# CS_JFETOnSemiSOT23_Simple_v1.net
KiCad netlist of a schematic drawn in Altium Designer
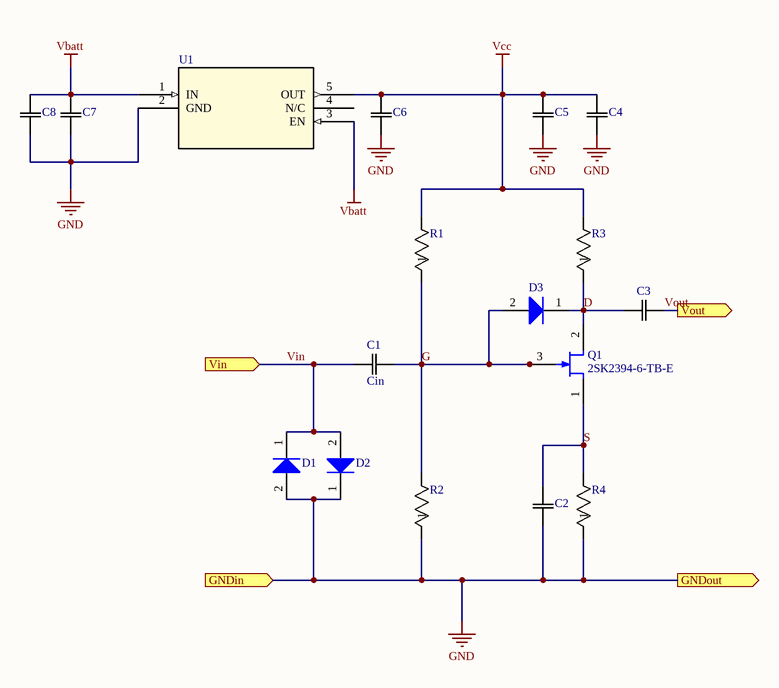
[diagram p0: CS_JFETOnSemiSOT23_Simple_v1.SchDoc]

(export (version "E")
  (design (tool "Eeschema 10.0.6"))
  (components
    (comp (ref "C1")
      (value "Cin")
      (footprint "C0201")
      (description "No Description Available")
      (fields
        (field (name "MANUFACTURER_PART_NUMBER") "C0201C270J3GACTU")
        (field (name "COPYRIGHT") "Copyright (C) 2018 Accelerated Designs. All rights reserved")
      )
      (libsource (lib "0201Capacitor_Yageo") (part "C0201C270J3GACTU"))
    )
    (comp (ref "C2")
      (value "~")
      (footprint "C0201")
      (description "No Description Available")
      (fields
        (field (name "MANUFACTURER_PART_NUMBER") "C0201C270J3GACTU")
        (field (name "COPYRIGHT") "Copyright (C) 2018 Accelerated Designs. All rights reserved")
      )
      (libsource (lib "0201Capacitor_Yageo") (part "C0201C270J3GACTU"))
    )
    (comp (ref "C3")
      (value "~")
      (footprint "C0201")
      (description "No Description Available")
      (fields
        (field (name "MANUFACTURER_PART_NUMBER") "C0201C270J3GACTU")
        (field (name "COPYRIGHT") "Copyright (C) 2018 Accelerated Designs. All rights reserved")
      )
      (libsource (lib "0201Capacitor_Yageo") (part "C0201C270J3GACTU"))
    )
    (comp (ref "C4")
      (value "~")
      (footprint "CAP_CBR_0201")
      (description "No Description Available")
      (fields
        (field (name "MANUFACTURER_PART_NUMBER") "CBR02C399C3GAC")
        (field (name "COPYRIGHT") "Copyright (C) 2018 Accelerated Designs. All rights reserved")
      )
      (libsource (lib "0201Capacitor_KEMET") (part "CBR02C399C3GAC"))
    )
    (comp (ref "C5")
      (value "~")
      (footprint "CAP_CBR_0201")
      (description "No Description Available")
      (fields
        (field (name "MANUFACTURER_PART_NUMBER") "CBR02C399C3GAC")
        (field (name "COPYRIGHT") "Copyright (C) 2018 Accelerated Designs. All rights reserved")
      )
      (libsource (lib "0201Capacitor_KEMET") (part "CBR02C399C3GAC"))
    )
    (comp (ref "C6")
      (value "~")
      (footprint "YAG_CC0402")
      (description "No Description Available")
      (fields
        (field (name "MANUFACTURER_PART_NUMBER") "CC0402KRX7R9BB103")
        (field (name "COPYRIGHT") "Copyright (C) 2018 Accelerated Designs. All rights reserved")
      )
      (libsource (lib "0402Capacitor_Yageo") (part "CC0402KRX7R9BB10"))
    )
    (comp (ref "C7")
      (value "~")
      (footprint "YAG_CC0402")
      (description "No Description Available")
      (fields
        (field (name "MANUFACTURER_PART_NUMBER") "CC0402KRX7R9BB103")
        (field (name "COPYRIGHT") "Copyright (C) 2018 Accelerated Designs. All rights reserved")
      )
      (libsource (lib "0402Capacitor_Yageo") (part "CC0402KRX7R9BB10"))
    )
    (comp (ref "C8")
      (value "~")
      (footprint "YAG_CC0402")
      (description "No Description Available")
      (fields
        (field (name "MANUFACTURER_PART_NUMBER") "CC0402KRX7R9BB103")
        (field (name "COPYRIGHT") "Copyright (C) 2018 Accelerated Designs. All rights reserved")
      )
      (libsource (lib "0402Capacitor_Yageo") (part "CC0402KRX7R9BB10"))
    )
    (comp (ref "D1")
      (value "~")
      (footprint "INF-SOD323_V")
      (description "Single Silicon Schottky Diode, 110 mA IF Max, SOD32, Green")
      (fields (field (name "MANUFACTURER") "Infineon") (field (name "PARTNUMBER") "BAT15-03W"))
      (libsource (lib "Infineon_RFSchottkyDiode_SOD323") (part "BAT15-03W"))
    )
    (comp (ref "D2")
      (value "~")
      (footprint "INF-SOD323_V")
      (description "Single Silicon Schottky Diode, 110 mA IF Max, SOD32, Green")
      (fields (field (name "MANUFACTURER") "Infineon") (field (name "PARTNUMBER") "BAT15-03W"))
      (libsource (lib "Infineon_RFSchottkyDiode_SOD323") (part "BAT15-03W"))
    )
    (comp (ref "D3")
      (value "~")
      (footprint "INF-SOD323_V")
      (description "Single Silicon Schottky Diode, 110 mA IF Max, SOD32, Green")
      (fields (field (name "MANUFACTURER") "Infineon") (field (name "PARTNUMBER") "BAT15-03W"))
      (libsource (lib "Infineon_RFSchottkyDiode_SOD323") (part "BAT15-03W"))
    )
    (comp (ref "Q1")
      (value "2SK2394-6-TB-E")
      (footprint "ONSC-CP-3-318AN_A_V")
      (description "N-Channel JFET, 15 V, 10 to 20 mA, 38 mS, 3-Pin CP, Pb-Free, Tape and Reel")
      (fields (field (name "MANUFACTURER") "On Semiconductor"))
      (libsource (lib "ON Semi JFETs") (part "2SK2394-6-TB-E"))
    )
    (comp (ref "R1")
      (value "~")
      (footprint "RES_RC0201_P6XP3")
      (description "No Description Available")
      (fields
        (field (name "MANUFACTURER_PART_NUMBER") "RC0201FR-0718KL")
        (field (name "COPYRIGHT") "Copyright (C) 2018 Accelerated Designs. All rights reserved")
      )
      (libsource (lib "0201Resistor_Yageo") (part "RC0201FR-0718KL"))
    )
    (comp (ref "R2")
      (value "~")
      (footprint "RES_RC0201_P6XP3")
      (description "No Description Available")
      (fields
        (field (name "MANUFACTURER_PART_NUMBER") "RC0201FR-0718KL")
        (field (name "COPYRIGHT") "Copyright (C) 2018 Accelerated Designs. All rights reserved")
      )
      (libsource (lib "0201Resistor_Yageo") (part "RC0201FR-0718KL"))
    )
    (comp (ref "R3")
      (value "~")
      (footprint "RES_RC0201_P6XP3")
      (description "No Description Available")
      (fields
        (field (name "MANUFACTURER_PART_NUMBER") "RC0201FR-0718KL")
        (field (name "COPYRIGHT") "Copyright (C) 2018 Accelerated Designs. All rights reserved")
      )
      (libsource (lib "0201Resistor_Yageo") (part "RC0201FR-0718KL"))
    )
    (comp (ref "R4")
      (value "~")
      (footprint "RES_RC0201_P6XP3")
      (description "No Description Available")
      (fields
        (field (name "MANUFACTURER_PART_NUMBER") "RC0201FR-0718KL")
        (field (name "COPYRIGHT") "Copyright (C) 2018 Accelerated Designs. All rights reserved")
      )
      (libsource (lib "0201Resistor_Yageo") (part "RC0201FR-0718KL"))
    )
    (comp (ref "U1")
      (value "~")
      (footprint "DBV5")
      (description "No Description Available")
      (fields
        (field (name "MANUFACTURER_PART_NUMBER") "LP5907MFX-3.3/NOPB")
        (field (name "COPYRIGHT") "Copyright (C) 2018 Accelerated Designs. All rights reserved")
      )
      (libsource (lib "TI_LDO_3V3_SOT325") (part "LP5907MFX-3.3/NO"))
    )
  )
  (nets
    (net (code "1") (name "/D") (class "Default")
      (node (ref "C3") (pin "1") (pinfunction "1_1") (pintype "passive"))
      (node (ref "D3") (pin "1") (pinfunction "K_1") (pintype "passive"))
      (node (ref "Q1") (pin "2") (pinfunction "D_2") (pintype "passive"))
      (node (ref "R3") (pin "1") (pinfunction "1_1") (pintype "passive"))
    )
    (net (code "2") (name "/G") (class "Default")
      (node (ref "C1") (pin "2") (pinfunction "2_2") (pintype "passive"))
      (node (ref "D3") (pin "2") (pinfunction "A_2") (pintype "passive"))
      (node (ref "Q1") (pin "3") (pinfunction "G_3") (pintype "passive"))
      (node (ref "R1") (pin "1") (pinfunction "1_1") (pintype "passive"))
      (node (ref "R2") (pin "2") (pinfunction "2_2") (pintype "passive"))
    )
    (net (code "3") (name "/S") (class "Default")
      (node (ref "C2") (pin "2") (pinfunction "2_2") (pintype "passive"))
      (node (ref "Q1") (pin "1") (pinfunction "S_1") (pintype "passive"))
      (node (ref "R4") (pin "2") (pinfunction "2_2") (pintype "passive"))
    )
    (net (code "4") (name "/Vin") (class "Default")
      (node (ref "C1") (pin "1") (pinfunction "1_1") (pintype "passive"))
      (node (ref "D1") (pin "1") (pinfunction "K_1") (pintype "passive"))
      (node (ref "D2") (pin "2") (pinfunction "A_2") (pintype "passive"))
    )
    (net (code "5") (name "/Vout") (class "Default")
      (node (ref "C3") (pin "2") (pinfunction "2_2") (pintype "passive"))
    )
    (net (code "6") (name "GND") (class "Default")
      (node (ref "C2") (pin "1") (pinfunction "1_1") (pintype "passive"))
      (node (ref "C4") (pin "1") (pinfunction "1_1") (pintype "passive"))
      (node (ref "C5") (pin "1") (pinfunction "1_1") (pintype "passive"))
      (node (ref "C6") (pin "1") (pinfunction "1_1") (pintype "passive"))
      (node (ref "C7") (pin "1") (pinfunction "1_1") (pintype "passive"))
      (node (ref "C8") (pin "1") (pinfunction "1_1") (pintype "passive"))
      (node (ref "D1") (pin "2") (pinfunction "A_2") (pintype "passive"))
      (node (ref "D2") (pin "1") (pinfunction "K_1") (pintype "passive"))
      (node (ref "R2") (pin "1") (pinfunction "1_1") (pintype "passive"))
      (node (ref "R4") (pin "1") (pinfunction "1_1") (pintype "passive"))
      (node (ref "U1") (pin "2") (pinfunction "GND_2") (pintype "power_in"))
    )
    (net (code "7") (name "Vbatt") (class "Default")
      (node (ref "C7") (pin "2") (pinfunction "2_2") (pintype "passive"))
      (node (ref "C8") (pin "2") (pinfunction "2_2") (pintype "passive"))
      (node (ref "U1") (pin "1") (pinfunction "IN_1") (pintype "input"))
      (node (ref "U1") (pin "3") (pinfunction "EN_3") (pintype "input"))
    )
    (net (code "8") (name "Vcc") (class "Default")
      (node (ref "C4") (pin "2") (pinfunction "2_2") (pintype "passive"))
      (node (ref "C5") (pin "2") (pinfunction "2_2") (pintype "passive"))
      (node (ref "C6") (pin "2") (pinfunction "2_2") (pintype "passive"))
      (node (ref "R1") (pin "2") (pinfunction "2_2") (pintype "passive"))
      (node (ref "R3") (pin "2") (pinfunction "2_2") (pintype "passive"))
      (node (ref "U1") (pin "5") (pinfunction "OUT_5") (pintype "output"))
    )
    (net (code "9") (name "unconnected-(U1-N{slash}C-Pad4)") (class "Default")
      (node (ref "U1") (pin "4") (pinfunction "N/C_4") (pintype "passive"))
    )
  )
)
